# board.net
KiCad netlist of a schematic drawn in EAGLE
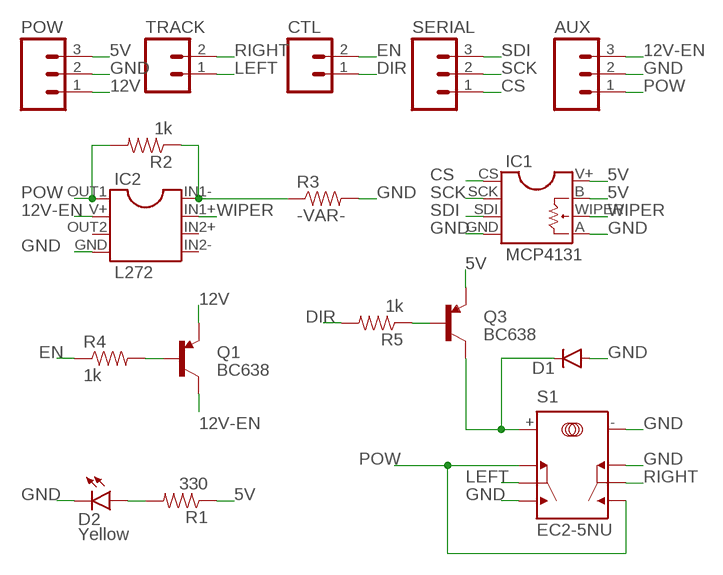
[diagram p0: schematic, sheet 1]

(export (version "E")
  (design (tool "Eeschema 10.0.6"))
  (components
    (comp (ref "AUX")
      (value "M03PTH")
      (footprint "eagle-import:1X03")
      (libsource (lib "eagle-import") (part "M03PTH"))
    )
    (comp (ref "CTL")
      (value "M02PTH")
      (footprint "eagle-import:1X02")
      (libsource (lib "eagle-import") (part "M02PTH"))
    )
    (comp (ref "D1")
      (value "DIODE1N4148")
      (footprint "eagle-import:DIODE-1N4148")
      (libsource (lib "eagle-import") (part "DIODE1N4148"))
    )
    (comp (ref "D2")
      (value "Yellow")
      (footprint "eagle-import:LED-EDGE")
      (libsource (lib "eagle-import") (part "LED-YELLOW0603"))
    )
    (comp (ref "IC1")
      (value "MCP4131")
      (footprint "eagle-import:MCP4131")
      (libsource (lib "eagle-import") (part "MCP4131"))
    )
    (comp (ref "IC2")
      (value "L272")
      (footprint "eagle-import:L272")
      (libsource (lib "eagle-import") (part "L272"))
    )
    (comp (ref "POW")
      (value "M03PTH")
      (footprint "eagle-import:1X03")
      (libsource (lib "eagle-import") (part "M03PTH"))
    )
    (comp (ref "Q1")
      (value "BC638")
      (footprint "eagle-import:TO-92")
      (libsource (lib "eagle-import") (part "TRANSISTOR_PNPTO92"))
    )
    (comp (ref "Q3")
      (value "BC638")
      (footprint "eagle-import:TO-92")
      (libsource (lib "eagle-import") (part "TRANSISTOR_PNPTO92"))
    )
    (comp (ref "R1")
      (value "330")
      (footprint "eagle-import:AXIAL-0.3")
      (libsource (lib "eagle-import") (part "1KOHM-1/4W-5%(PTH)"))
    )
    (comp (ref "R2")
      (value "1k")
      (footprint "eagle-import:AXIAL-0.3")
      (libsource (lib "eagle-import") (part "1KOHM-1/4W-5%(PTH)"))
    )
    (comp (ref "R3")
      (value "-VAR-")
      (footprint "eagle-import:AXIAL-0.3")
      (libsource (lib "eagle-import") (part "1KOHM-1/4W-5%(PTH)"))
    )
    (comp (ref "R4")
      (value "1k")
      (footprint "eagle-import:AXIAL-0.3")
      (libsource (lib "eagle-import") (part "1KOHM-1/4W-5%(PTH)"))
    )
    (comp (ref "R5")
      (value "1k")
      (footprint "eagle-import:AXIAL-0.3")
      (libsource (lib "eagle-import") (part "1KOHM-1/4W-5%(PTH)"))
    )
    (comp (ref "S1")
      (value "EC2-5NU")
      (footprint "eagle-import:EC2-5NU")
      (libsource (lib "eagle-import") (part "EC2-5NU"))
    )
    (comp (ref "SERIAL")
      (value "M03PTH")
      (footprint "eagle-import:1X03")
      (libsource (lib "eagle-import") (part "M03PTH"))
    )
    (comp (ref "TRACK")
      (value "M02PTH")
      (footprint "eagle-import:1X02")
      (libsource (lib "eagle-import") (part "M02PTH"))
    )
  )
  (nets
    (net (code "1") (name "/5V") (class "Default")
      (node (ref "IC1") (pin "B") (pinfunction "B_B") (pintype "bidirectional"))
      (node (ref "IC1") (pin "V+") (pinfunction "V+_V+") (pintype "bidirectional"))
      (node (ref "POW") (pin "3") (pinfunction "3_3") (pintype "passive"))
      (node (ref "Q3") (pin "1") (pinfunction "E_1") (pintype "passive"))
      (node (ref "R1") (pin "P$1") (pinfunction "1_P$1") (pintype "passive"))
    )
    (net (code "2") (name "/12V") (class "Default")
      (node (ref "POW") (pin "1") (pinfunction "1_1") (pintype "passive"))
      (node (ref "Q1") (pin "1") (pinfunction "E_1") (pintype "passive"))
    )
    (net (code "3") (name "/12V-EN") (class "Default")
      (node (ref "AUX") (pin "3") (pinfunction "3_3") (pintype "passive"))
      (node (ref "IC2") (pin "V+") (pinfunction "V+_V+") (pintype "bidirectional"))
      (node (ref "Q1") (pin "3") (pinfunction "C_3") (pintype "passive"))
    )
    (net (code "4") (name "/CS") (class "Default")
      (node (ref "IC1") (pin "CS") (pinfunction "CS_CS") (pintype "bidirectional"))
      (node (ref "SERIAL") (pin "1") (pinfunction "1_1") (pintype "passive"))
    )
    (net (code "5") (name "/DIR") (class "Default")
      (node (ref "CTL") (pin "1") (pinfunction "1_1") (pintype "passive"))
      (node (ref "R5") (pin "P$2") (pinfunction "2_P$2") (pintype "passive"))
    )
    (net (code "6") (name "/EN") (class "Default")
      (node (ref "CTL") (pin "2") (pinfunction "2_2") (pintype "passive"))
      (node (ref "R4") (pin "P$1") (pinfunction "1_P$1") (pintype "passive"))
    )
    (net (code "7") (name "/GND") (class "Default")
      (node (ref "AUX") (pin "2") (pinfunction "2_2") (pintype "passive"))
      (node (ref "D1") (pin "A") (pinfunction "A_A") (pintype "passive"))
      (node (ref "D2") (pin "C") (pinfunction "C_C") (pintype "passive"))
      (node (ref "IC1") (pin "A") (pinfunction "A_A") (pintype "bidirectional"))
      (node (ref "IC1") (pin "GND") (pinfunction "GND_GND") (pintype "bidirectional"))
      (node (ref "IC2") (pin "GND") (pinfunction "GND_GND") (pintype "bidirectional"))
      (node (ref "POW") (pin "2") (pinfunction "2_2") (pintype "passive"))
      (node (ref "R3") (pin "P$2") (pinfunction "2_P$2") (pintype "passive"))
      (node (ref "S1") (pin "-") (pinfunction "-_-") (pintype "power_in"))
      (node (ref "S1") (pin "NC2") (pinfunction "NC2_NC2") (pintype "bidirectional"))
      (node (ref "S1") (pin "NO1") (pinfunction "NO1_NO1") (pintype "bidirectional"))
    )
    (net (code "8") (name "/LEFT") (class "Default")
      (node (ref "S1") (pin "COM1") (pinfunction "COM1_COM1") (pintype "bidirectional"))
      (node (ref "TRACK") (pin "1") (pinfunction "1_1") (pintype "passive"))
    )
    (net (code "9") (name "/POW") (class "Default")
      (node (ref "AUX") (pin "1") (pinfunction "1_1") (pintype "passive"))
      (node (ref "IC2") (pin "OUT1") (pinfunction "OUT1_OUT1") (pintype "bidirectional"))
      (node (ref "R2") (pin "P$2") (pinfunction "2_P$2") (pintype "passive"))
      (node (ref "S1") (pin "NC1") (pinfunction "NC1_NC1") (pintype "bidirectional"))
      (node (ref "S1") (pin "NO2") (pinfunction "NO2_NO2") (pintype "bidirectional"))
    )
    (net (code "10") (name "/RIGHT") (class "Default")
      (node (ref "S1") (pin "COM2") (pinfunction "COM2_COM2") (pintype "bidirectional"))
      (node (ref "TRACK") (pin "2") (pinfunction "2_2") (pintype "passive"))
    )
    (net (code "11") (name "/SCK") (class "Default")
      (node (ref "IC1") (pin "SCK") (pinfunction "SCK_SCK") (pintype "bidirectional"))
      (node (ref "SERIAL") (pin "2") (pinfunction "2_2") (pintype "passive"))
    )
    (net (code "12") (name "/SDI") (class "Default")
      (node (ref "IC1") (pin "SDI") (pinfunction "SDI_SDI") (pintype "bidirectional"))
      (node (ref "SERIAL") (pin "3") (pinfunction "3_3") (pintype "passive"))
    )
    (net (code "13") (name "/WIPER") (class "Default")
      (node (ref "IC1") (pin "WIPER") (pinfunction "WIPER_WIPER") (pintype "bidirectional"))
      (node (ref "IC2") (pin "IN1+") (pinfunction "IN1+_IN1+") (pintype "bidirectional"))
    )
    (net (code "14") (name "Net-(Q1-B)") (class "Default")
      (node (ref "Q1") (pin "2") (pinfunction "B_2") (pintype "passive"))
      (node (ref "R4") (pin "P$2") (pinfunction "2_P$2") (pintype "passive"))
    )
    (net (code "15") (name "Net-(Q3-B)") (class "Default")
      (node (ref "Q3") (pin "2") (pinfunction "B_2") (pintype "passive"))
      (node (ref "R5") (pin "P$1") (pinfunction "1_P$1") (pintype "passive"))
    )
    (net (code "16") (name "Net-(Q3-C)") (class "Default")
      (node (ref "D1") (pin "C") (pinfunction "C_C") (pintype "passive"))
      (node (ref "Q3") (pin "3") (pinfunction "C_3") (pintype "passive"))
      (node (ref "S1") (pin "+") (pinfunction "+_+") (pintype "power_in"))
    )
    (net (code "17") (name "Net-(R1-2)") (class "Default")
      (node (ref "D2") (pin "A") (pinfunction "A_A") (pintype "passive"))
      (node (ref "R1") (pin "P$2") (pinfunction "2_P$2") (pintype "passive"))
    )
    (net (code "18") (name "Net-(R2-1)") (class "Default")
      (node (ref "IC2") (pin "IN1-") (pinfunction "IN1-_IN1-") (pintype "bidirectional"))
      (node (ref "R2") (pin "P$1") (pinfunction "1_P$1") (pintype "passive"))
      (node (ref "R3") (pin "P$1") (pinfunction "1_P$1") (pintype "passive"))
    )
    (net (code "19") (name "unconnected-(IC2-PadIN2+)") (class "Default")
      (node (ref "IC2") (pin "IN2+") (pinfunction "IN2+_IN2+") (pintype "bidirectional"))
    )
    (net (code "20") (name "unconnected-(IC2-PadIN2-)") (class "Default")
      (node (ref "IC2") (pin "IN2-") (pinfunction "IN2-_IN2-") (pintype "bidirectional"))
    )
    (net (code "21") (name "unconnected-(IC2-PadOUT2)") (class "Default")
      (node (ref "IC2") (pin "OUT2") (pinfunction "OUT2_OUT2") (pintype "bidirectional"))
    )
  )
)
